# Diode_Reverse_Recovery_Test_Circuit.net
KiCad netlist of a schematic drawn in Altium Designer
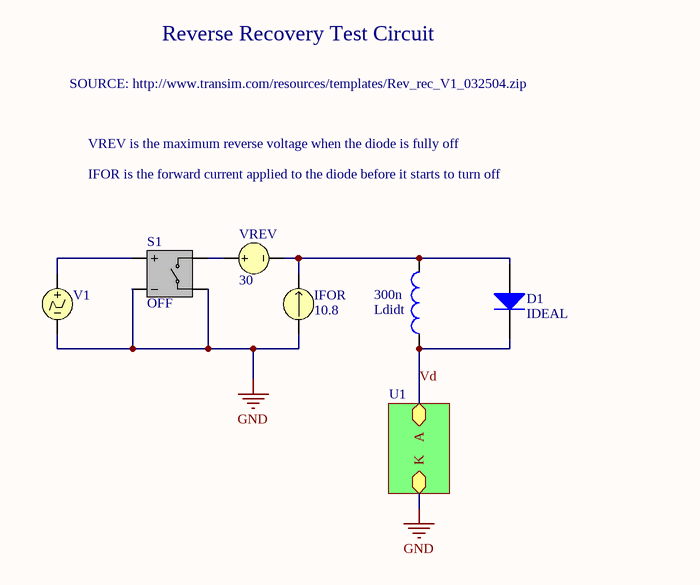
[diagram p0: Diode Reverse Recovery Test Circuit.SchDoc]

(export (version "E")
  (design (tool "Eeschema 10.0.6"))
  (components
    (comp (ref "D1")
      (value "IDEAL")
      (footprint "SMC")
      (description "Default Diode")
      (fields (field (name "PUBLISHER") "Altium Limited"))
      (libsource (lib "Miscellaneous Devices") (part "Diode"))
    )
    (comp (ref "IFOR")
      (value "10.8")
      (description "Current Source")
      (fields (field (name "PUBLISHER") "Altium Limited"))
      (libsource (lib "Simulation Sources") (part "ISRC"))
    )
    (comp (ref "Ldidt")
      (value "300n")
      (footprint "0402-A")
      (description "Inductor")
      (fields (field (name "PUBLISHER") "Altium Limited"))
      (libsource (lib "Miscellaneous Devices") (part "Inductor"))
    )
    (comp (ref "S1")
      (value "VSW")
      (description "Voltage Controlled Switch")
      (fields (field (name "INITIAL CONDITION") "OFF") (field (name "PUBLISHER") "Altium Limited"))
      (libsource (lib "Simulation Special Function") (part "VSW"))
    )
    (comp (ref "V1")
      (value "VPWL")
      (description "Piecewise Linear Voltage Source")
      (fields (field (name "PUBLISHER") "Altium Limited"))
      (libsource (lib "Simulation Sources") (part "VPWL"))
    )
    (comp (ref "VREV")
      (value "30")
      (description "Voltage Source")
      (fields (field (name "PUBLISHER") "Altium Limited"))
      (libsource (lib "Simulation Sources") (part "VSRC"))
    )
  )
  (nets
    (net (code "1") (name "/Vd") (class "Default")
      (node (ref "D1") (pin "2") (pinfunction "K_2") (pintype "passive"))
      (node (ref "Ldidt") (pin "1") (pinfunction "1_1") (pintype "passive"))
    )
    (net (code "2") (name "GND") (class "Default")
      (node (ref "IFOR") (pin "1") (pinfunction "1_1") (pintype "passive"))
      (node (ref "S1") (pin "2") (pinfunction "N1-_2") (pintype "passive"))
      (node (ref "S1") (pin "4") (pinfunction "N2-_4") (pintype "passive"))
      (node (ref "V1") (pin "2") (pinfunction "2_2") (pintype "passive"))
    )
    (net (code "3") (name "Net-(D1-A)") (class "Default")
      (node (ref "D1") (pin "1") (pinfunction "A_1") (pintype "passive"))
      (node (ref "IFOR") (pin "2") (pinfunction "2_2") (pintype "passive"))
      (node (ref "Ldidt") (pin "2") (pinfunction "2_2") (pintype "passive"))
      (node (ref "VREV") (pin "2") (pinfunction "2_2") (pintype "passive"))
    )
    (net (code "4") (name "Net-(S1-N1+)") (class "Default")
      (node (ref "S1") (pin "1") (pinfunction "N1+_1") (pintype "passive"))
      (node (ref "V1") (pin "1") (pinfunction "1_1") (pintype "passive"))
    )
    (net (code "5") (name "Net-(S1-N2+)") (class "Default")
      (node (ref "S1") (pin "3") (pinfunction "N2+_3") (pintype "passive"))
      (node (ref "VREV") (pin "1") (pinfunction "1_1") (pintype "passive"))
    )
  )
)
